# RK3399_SDRAM.net
KiCad netlist of a schematic drawn in Altium Designer
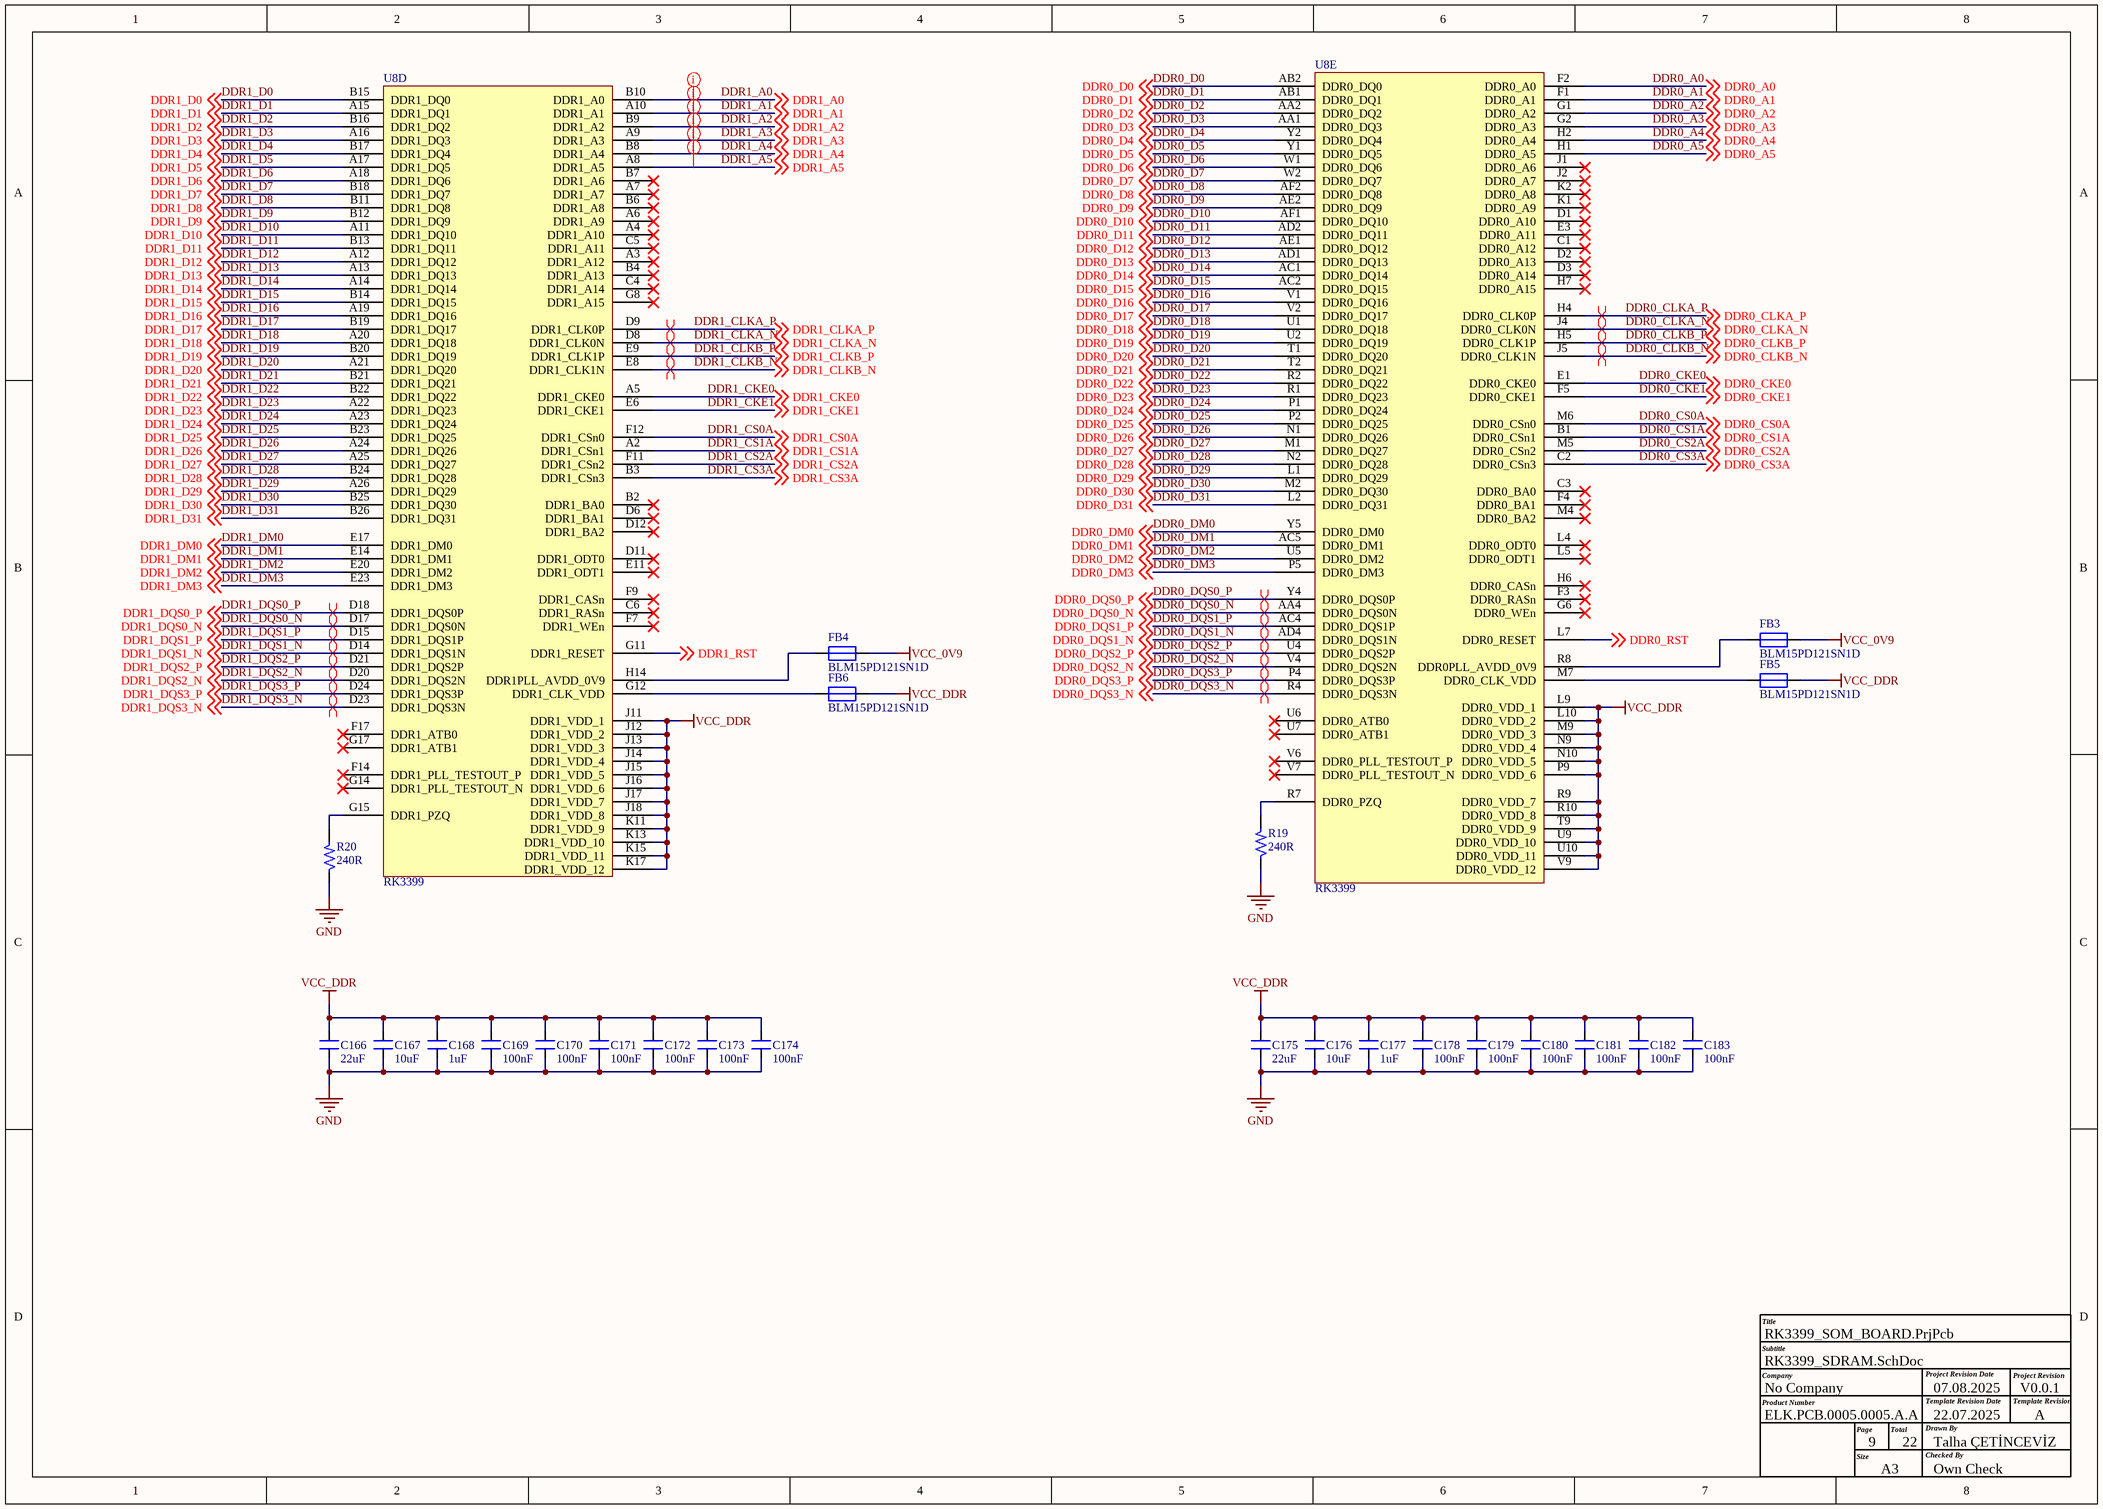
[diagram p0: RK3399_SDRAM.SchDoc]

(export (version "E")
  (design (tool "Eeschema 10.0.6"))
  (components
    (comp (ref "C166")
      (value "22uF")
      (footprint "CAP_0402")
      (description "22µF ±20% 6.3V Ceramic Capacitor X5R 0402 (1005 Metric)")
      (fields
        (field (name "MANUFACTURER") "Murata Electronics")
        (field (name "MANUFACTURER PART NUMBER") "CL05A226MQ5N6J8")
      )
      (libsource (lib "EsteemPCB_SOM_Course_intlib") (part "CAP_22uF-6.3V-20%-0402"))
    )
    (comp (ref "C167")
      (value "10uF")
      (footprint "CAP_0402")
      (description "10µF ±20% 10V Ceramic Capacitor X5R 0402 (1005 Metric)")
      (fields
        (field (name "MANUFACTURER PART NUMBER") "CL05A106MP5NUNC")
        (field (name "MANUFACTURER") "Samsung Electro-Mechanics")
      )
      (libsource (lib "EsteemPCB_SOM_Course_intlib") (part "CAP_10uF-10V-20%-0402"))
    )
    (comp (ref "C168")
      (value "1uF")
      (footprint "CAP_0201")
      (description "1µF ±20% 16V Ceramic Capacitor X5R 0201 (0603 Metric)")
      (fields
        (field (name "MANUFACTURER") "Samsung Electro-Mechanics")
        (field (name "MANUFACTURER PART NUMBER") "CL03A105MO3NRNH")
      )
      (libsource (lib "EsteemPCB_SOM_Course_intlib") (part "CAP_1uF-16V-10%-0201"))
    )
    (comp (ref "C169")
      (value "100nF")
      (footprint "CAP_0201")
      (description "0.1µF ±10% 25V Ceramic Capacitor X5R 0201 (0603 Metric)")
      (fields
        (field (name "MANUFACTURER") "TDK Corporation")
        (field (name "MANUFACTURER PART NUMBER") "C0603X5R1E104K030BB")
      )
      (libsource (lib "EsteemPCB_SOM_Course_intlib") (part "CAP_100nF-25V-10%-0201"))
    )
    (comp (ref "C170")
      (value "100nF")
      (footprint "CAP_0201")
      (description "0.1µF ±10% 25V Ceramic Capacitor X5R 0201 (0603 Metric)")
      (fields
        (field (name "MANUFACTURER") "TDK Corporation")
        (field (name "MANUFACTURER PART NUMBER") "C0603X5R1E104K030BB")
      )
      (libsource (lib "EsteemPCB_SOM_Course_intlib") (part "CAP_100nF-25V-10%-0201"))
    )
    (comp (ref "C171")
      (value "100nF")
      (footprint "CAP_0201")
      (description "0.1µF ±10% 25V Ceramic Capacitor X5R 0201 (0603 Metric)")
      (fields
        (field (name "MANUFACTURER") "TDK Corporation")
        (field (name "MANUFACTURER PART NUMBER") "C0603X5R1E104K030BB")
      )
      (libsource (lib "EsteemPCB_SOM_Course_intlib") (part "CAP_100nF-25V-10%-0201"))
    )
    (comp (ref "C172")
      (value "100nF")
      (footprint "CAP_0201")
      (description "0.1µF ±10% 25V Ceramic Capacitor X5R 0201 (0603 Metric)")
      (fields
        (field (name "MANUFACTURER") "TDK Corporation")
        (field (name "MANUFACTURER PART NUMBER") "C0603X5R1E104K030BB")
      )
      (libsource (lib "EsteemPCB_SOM_Course_intlib") (part "CAP_100nF-25V-10%-0201"))
    )
    (comp (ref "C173")
      (value "100nF")
      (footprint "CAP_0201")
      (description "0.1µF ±10% 25V Ceramic Capacitor X5R 0201 (0603 Metric)")
      (fields
        (field (name "MANUFACTURER") "TDK Corporation")
        (field (name "MANUFACTURER PART NUMBER") "C0603X5R1E104K030BB")
      )
      (libsource (lib "EsteemPCB_SOM_Course_intlib") (part "CAP_100nF-25V-10%-0201"))
    )
    (comp (ref "C174")
      (value "100nF")
      (footprint "CAP_0201")
      (description "0.1µF ±10% 25V Ceramic Capacitor X5R 0201 (0603 Metric)")
      (fields
        (field (name "MANUFACTURER") "TDK Corporation")
        (field (name "MANUFACTURER PART NUMBER") "C0603X5R1E104K030BB")
      )
      (libsource (lib "EsteemPCB_SOM_Course_intlib") (part "CAP_100nF-25V-10%-0201"))
    )
    (comp (ref "C175")
      (value "22uF")
      (footprint "CAP_0402")
      (description "22µF ±20% 6.3V Ceramic Capacitor X5R 0402 (1005 Metric)")
      (fields
        (field (name "MANUFACTURER") "Murata Electronics")
        (field (name "MANUFACTURER PART NUMBER") "CL05A226MQ5N6J8")
      )
      (libsource (lib "EsteemPCB_SOM_Course_intlib") (part "CAP_22uF-6.3V-20%-0402"))
    )
    (comp (ref "C176")
      (value "10uF")
      (footprint "CAP_0402")
      (description "10µF ±20% 10V Ceramic Capacitor X5R 0402 (1005 Metric)")
      (fields
        (field (name "MANUFACTURER PART NUMBER") "CL05A106MP5NUNC")
        (field (name "MANUFACTURER") "Samsung Electro-Mechanics")
      )
      (libsource (lib "EsteemPCB_SOM_Course_intlib") (part "CAP_10uF-10V-20%-0402"))
    )
    (comp (ref "C177")
      (value "1uF")
      (footprint "CAP_0201")
      (description "1µF ±20% 16V Ceramic Capacitor X5R 0201 (0603 Metric)")
      (fields
        (field (name "MANUFACTURER") "Samsung Electro-Mechanics")
        (field (name "MANUFACTURER PART NUMBER") "CL03A105MO3NRNH")
      )
      (libsource (lib "EsteemPCB_SOM_Course_intlib") (part "CAP_1uF-16V-10%-0201"))
    )
    (comp (ref "C178")
      (value "100nF")
      (footprint "CAP_0201")
      (description "0.1µF ±10% 25V Ceramic Capacitor X5R 0201 (0603 Metric)")
      (fields
        (field (name "MANUFACTURER") "TDK Corporation")
        (field (name "MANUFACTURER PART NUMBER") "C0603X5R1E104K030BB")
      )
      (libsource (lib "EsteemPCB_SOM_Course_intlib") (part "CAP_100nF-25V-10%-0201"))
    )
    (comp (ref "C179")
      (value "100nF")
      (footprint "CAP_0201")
      (description "0.1µF ±10% 25V Ceramic Capacitor X5R 0201 (0603 Metric)")
      (fields
        (field (name "MANUFACTURER") "TDK Corporation")
        (field (name "MANUFACTURER PART NUMBER") "C0603X5R1E104K030BB")
      )
      (libsource (lib "EsteemPCB_SOM_Course_intlib") (part "CAP_100nF-25V-10%-0201"))
    )
    (comp (ref "C180")
      (value "100nF")
      (footprint "CAP_0201")
      (description "0.1µF ±10% 25V Ceramic Capacitor X5R 0201 (0603 Metric)")
      (fields
        (field (name "MANUFACTURER") "TDK Corporation")
        (field (name "MANUFACTURER PART NUMBER") "C0603X5R1E104K030BB")
      )
      (libsource (lib "EsteemPCB_SOM_Course_intlib") (part "CAP_100nF-25V-10%-0201"))
    )
    (comp (ref "C181")
      (value "100nF")
      (footprint "CAP_0201")
      (description "0.1µF ±10% 25V Ceramic Capacitor X5R 0201 (0603 Metric)")
      (fields
        (field (name "MANUFACTURER") "TDK Corporation")
        (field (name "MANUFACTURER PART NUMBER") "C0603X5R1E104K030BB")
      )
      (libsource (lib "EsteemPCB_SOM_Course_intlib") (part "CAP_100nF-25V-10%-0201"))
    )
    (comp (ref "C182")
      (value "100nF")
      (footprint "CAP_0201")
      (description "0.1µF ±10% 25V Ceramic Capacitor X5R 0201 (0603 Metric)")
      (fields
        (field (name "MANUFACTURER") "TDK Corporation")
        (field (name "MANUFACTURER PART NUMBER") "C0603X5R1E104K030BB")
      )
      (libsource (lib "EsteemPCB_SOM_Course_intlib") (part "CAP_100nF-25V-10%-0201"))
    )
    (comp (ref "C183")
      (value "100nF")
      (footprint "CAP_0201")
      (description "0.1µF ±10% 25V Ceramic Capacitor X5R 0201 (0603 Metric)")
      (fields
        (field (name "MANUFACTURER") "TDK Corporation")
        (field (name "MANUFACTURER PART NUMBER") "C0603X5R1E104K030BB")
      )
      (libsource (lib "EsteemPCB_SOM_Course_intlib") (part "CAP_100nF-25V-10%-0201"))
    )
    (comp (ref "FB3")
      (value "BLM15PD121SN1D")
      (footprint "RES_0402")
      (description "120 Ohms @ 100MHz 1 Power Line Ferrite Bead 0402 (1005 Metric) 1.3A 90mOhm")
      (fields (field (name "MANUFACTURER") "Murata Electronics"))
      (libsource (lib "EsteemPCB_SOM_Course_intlib") (part "FB_120R-1.3A-100Mhz-0402"))
    )
    (comp (ref "FB4")
      (value "BLM15PD121SN1D")
      (footprint "RES_0402")
      (description "120 Ohms @ 100MHz 1 Power Line Ferrite Bead 0402 (1005 Metric) 1.3A 90mOhm")
      (fields (field (name "MANUFACTURER") "Murata Electronics"))
      (libsource (lib "EsteemPCB_SOM_Course_intlib") (part "FB_120R-1.3A-100Mhz-0402"))
    )
    (comp (ref "FB5")
      (value "BLM15PD121SN1D")
      (footprint "RES_0402")
      (description "120 Ohms @ 100MHz 1 Power Line Ferrite Bead 0402 (1005 Metric) 1.3A 90mOhm")
      (fields (field (name "MANUFACTURER") "Murata Electronics"))
      (libsource (lib "EsteemPCB_SOM_Course_intlib") (part "FB_120R-1.3A-100Mhz-0402"))
    )
    (comp (ref "FB6")
      (value "BLM15PD121SN1D")
      (footprint "RES_0402")
      (description "120 Ohms @ 100MHz 1 Power Line Ferrite Bead 0402 (1005 Metric) 1.3A 90mOhm")
      (fields (field (name "MANUFACTURER") "Murata Electronics"))
      (libsource (lib "EsteemPCB_SOM_Course_intlib") (part "FB_120R-1.3A-100Mhz-0402"))
    )
    (comp (ref "R19")
      (value "240R")
      (footprint "RES_0201")
      (description "240 Ohms ±1% 0.05W, 1/20W Chip Resistor 0201 (0603 Metric) Thick Film")
      (fields
        (field (name "MANUFACTURER") "Yageo")
        (field (name "MANUFACTURER PART NUMBER") "RC0201FR-07240RL")
      )
      (libsource (lib "EsteemPCB_SOM_Course_intlib") (part "RES_240R-0.05W-1%-0201"))
    )
    (comp (ref "R20")
      (value "240R")
      (footprint "RES_0201")
      (description "240 Ohms ±1% 0.05W, 1/20W Chip Resistor 0201 (0603 Metric) Thick Film")
      (fields
        (field (name "MANUFACTURER") "Yageo")
        (field (name "MANUFACTURER PART NUMBER") "RC0201FR-07240RL")
      )
      (libsource (lib "EsteemPCB_SOM_Course_intlib") (part "RES_240R-0.05W-1%-0201"))
    )
    (comp (ref "U8")
      (value "RK3399")
      (footprint "FBGA828_23_826X826")
      (description "RK3399 is a low power, high performance processor for computing, personal mobile.")
      (fields (field (name "MANUFACTURER") "Rockchip"))
      (libsource (lib "EsteemPCB_SOM_Course_intlib") (part "IC_RK3399-FCBGA828"))
    )
  )
  (nets
    (net (code "1") (name "DDR0_A0") (class "Default")
      (node (ref "U8") (pin "F2") (pinfunction "DDR0_A0_F2") (pintype "passive"))
    )
    (net (code "2") (name "DDR0_A1") (class "Default")
      (node (ref "U8") (pin "F1") (pinfunction "DDR0_A1_F1") (pintype "passive"))
    )
    (net (code "3") (name "DDR0_A2") (class "Default")
      (node (ref "U8") (pin "G1") (pinfunction "DDR0_A2_G1") (pintype "passive"))
    )
    (net (code "4") (name "DDR0_A3") (class "Default")
      (node (ref "U8") (pin "G2") (pinfunction "DDR0_A3_G2") (pintype "passive"))
    )
    (net (code "5") (name "DDR0_A4") (class "Default")
      (node (ref "U8") (pin "H2") (pinfunction "DDR0_A4_H2") (pintype "passive"))
    )
    (net (code "6") (name "DDR0_A5") (class "Default")
      (node (ref "U8") (pin "H1") (pinfunction "DDR0_A5_H1") (pintype "passive"))
    )
    (net (code "7") (name "DDR0_CKE0") (class "Default")
      (node (ref "U8") (pin "E1") (pinfunction "DDR0_CKE0_E1") (pintype "passive"))
    )
    (net (code "8") (name "DDR0_CKE1") (class "Default")
      (node (ref "U8") (pin "F5") (pinfunction "DDR0_CKE1_F5") (pintype "passive"))
    )
    (net (code "9") (name "DDR0_CLKA_N") (class "Default")
      (node (ref "U8") (pin "J4") (pinfunction "DDR0_CLK0N_J4") (pintype "passive"))
    )
    (net (code "10") (name "DDR0_CLKA_P") (class "Default")
      (node (ref "U8") (pin "H4") (pinfunction "DDR0_CLK0P_H4") (pintype "passive"))
    )
    (net (code "11") (name "DDR0_CLKB_N") (class "Default")
      (node (ref "U8") (pin "J5") (pinfunction "DDR0_CLK1N_J5") (pintype "passive"))
    )
    (net (code "12") (name "DDR0_CLKB_P") (class "Default")
      (node (ref "U8") (pin "H5") (pinfunction "DDR0_CLK1P_H5") (pintype "passive"))
    )
    (net (code "13") (name "DDR0_CS0A") (class "Default")
      (node (ref "U8") (pin "M6") (pinfunction "DDR0_CSn0_M6") (pintype "passive"))
    )
    (net (code "14") (name "DDR0_CS1A") (class "Default")
      (node (ref "U8") (pin "B1") (pinfunction "DDR0_CSn1_B1") (pintype "passive"))
    )
    (net (code "15") (name "DDR0_CS2A") (class "Default")
      (node (ref "U8") (pin "M5") (pinfunction "DDR0_CSn2_M5") (pintype "passive"))
    )
    (net (code "16") (name "DDR0_CS3A") (class "Default")
      (node (ref "U8") (pin "C2") (pinfunction "DDR0_CSn3_C2") (pintype "passive"))
    )
    (net (code "17") (name "DDR0_D0") (class "Default")
      (node (ref "U8") (pin "AB2") (pinfunction "DDR0_DQ0_AB2") (pintype "passive"))
    )
    (net (code "18") (name "DDR0_D1") (class "Default")
      (node (ref "U8") (pin "AB1") (pinfunction "DDR0_DQ1_AB1") (pintype "passive"))
    )
    (net (code "19") (name "DDR0_D2") (class "Default")
      (node (ref "U8") (pin "AA2") (pinfunction "DDR0_DQ2_AA2") (pintype "passive"))
    )
    (net (code "20") (name "DDR0_D3") (class "Default")
      (node (ref "U8") (pin "AA1") (pinfunction "DDR0_DQ3_AA1") (pintype "passive"))
    )
    (net (code "21") (name "DDR0_D4") (class "Default")
      (node (ref "U8") (pin "Y2") (pinfunction "DDR0_DQ4_Y2") (pintype "passive"))
    )
    (net (code "22") (name "DDR0_D5") (class "Default")
      (node (ref "U8") (pin "Y1") (pinfunction "DDR0_DQ5_Y1") (pintype "passive"))
    )
    (net (code "23") (name "DDR0_D6") (class "Default")
      (node (ref "U8") (pin "W1") (pinfunction "DDR0_DQ6_W1") (pintype "passive"))
    )
    (net (code "24") (name "DDR0_D7") (class "Default")
      (node (ref "U8") (pin "W2") (pinfunction "DDR0_DQ7_W2") (pintype "passive"))
    )
    (net (code "25") (name "DDR0_D8") (class "Default")
      (node (ref "U8") (pin "AF2") (pinfunction "DDR0_DQ8_AF2") (pintype "passive"))
    )
    (net (code "26") (name "DDR0_D9") (class "Default")
      (node (ref "U8") (pin "AE2") (pinfunction "DDR0_DQ9_AE2") (pintype "passive"))
    )
    (net (code "27") (name "DDR0_D10") (class "Default")
      (node (ref "U8") (pin "AF1") (pinfunction "DDR0_DQ10_AF1") (pintype "passive"))
    )
    (net (code "28") (name "DDR0_D11") (class "Default")
      (node (ref "U8") (pin "AD2") (pinfunction "DDR0_DQ11_AD2") (pintype "passive"))
    )
    (net (code "29") (name "DDR0_D12") (class "Default")
      (node (ref "U8") (pin "AE1") (pinfunction "DDR0_DQ12_AE1") (pintype "passive"))
    )
    (net (code "30") (name "DDR0_D13") (class "Default")
      (node (ref "U8") (pin "AD1") (pinfunction "DDR0_DQ13_AD1") (pintype "passive"))
    )
    (net (code "31") (name "DDR0_D14") (class "Default")
      (node (ref "U8") (pin "AC1") (pinfunction "DDR0_DQ14_AC1") (pintype "passive"))
    )
    (net (code "32") (name "DDR0_D15") (class "Default")
      (node (ref "U8") (pin "AC2") (pinfunction "DDR0_DQ15_AC2") (pintype "passive"))
    )
    (net (code "33") (name "DDR0_D16") (class "Default")
      (node (ref "U8") (pin "V1") (pinfunction "DDR0_DQ16_V1") (pintype "passive"))
    )
    (net (code "34") (name "DDR0_D17") (class "Default")
      (node (ref "U8") (pin "V2") (pinfunction "DDR0_DQ17_V2") (pintype "passive"))
    )
    (net (code "35") (name "DDR0_D18") (class "Default")
      (node (ref "U8") (pin "U1") (pinfunction "DDR0_DQ18_U1") (pintype "passive"))
    )
    (net (code "36") (name "DDR0_D19") (class "Default")
      (node (ref "U8") (pin "U2") (pinfunction "DDR0_DQ19_U2") (pintype "passive"))
    )
    (net (code "37") (name "DDR0_D20") (class "Default")
      (node (ref "U8") (pin "T1") (pinfunction "DDR0_DQ20_T1") (pintype "passive"))
    )
    (net (code "38") (name "DDR0_D21") (class "Default")
      (node (ref "U8") (pin "T2") (pinfunction "DDR0_DQ21_T2") (pintype "passive"))
    )
    (net (code "39") (name "DDR0_D22") (class "Default")
      (node (ref "U8") (pin "R2") (pinfunction "DDR0_DQ22_R2") (pintype "passive"))
    )
    (net (code "40") (name "DDR0_D23") (class "Default")
      (node (ref "U8") (pin "R1") (pinfunction "DDR0_DQ23_R1") (pintype "passive"))
    )
    (net (code "41") (name "DDR0_D24") (class "Default")
      (node (ref "U8") (pin "P1") (pinfunction "DDR0_DQ24_P1") (pintype "passive"))
    )
    (net (code "42") (name "DDR0_D25") (class "Default")
      (node (ref "U8") (pin "P2") (pinfunction "DDR0_DQ25_P2") (pintype "passive"))
    )
    (net (code "43") (name "DDR0_D26") (class "Default")
      (node (ref "U8") (pin "N1") (pinfunction "DDR0_DQ26_N1") (pintype "passive"))
    )
    (net (code "44") (name "DDR0_D27") (class "Default")
      (node (ref "U8") (pin "M1") (pinfunction "DDR0_DQ27_M1") (pintype "passive"))
    )
    (net (code "45") (name "DDR0_D28") (class "Default")
      (node (ref "U8") (pin "N2") (pinfunction "DDR0_DQ28_N2") (pintype "passive"))
    )
    (net (code "46") (name "DDR0_D29") (class "Default")
      (node (ref "U8") (pin "L1") (pinfunction "DDR0_DQ29_L1") (pintype "passive"))
    )
    (net (code "47") (name "DDR0_D30") (class "Default")
      (node (ref "U8") (pin "M2") (pinfunction "DDR0_DQ30_M2") (pintype "passive"))
    )
    (net (code "48") (name "DDR0_D31") (class "Default")
      (node (ref "U8") (pin "L2") (pinfunction "DDR0_DQ31_L2") (pintype "passive"))
    )
    (net (code "49") (name "DDR0_DM0") (class "Default")
      (node (ref "U8") (pin "Y5") (pinfunction "DDR0_DM0_Y5") (pintype "passive"))
    )
    (net (code "50") (name "DDR0_DM1") (class "Default")
      (node (ref "U8") (pin "AC5") (pinfunction "DDR0_DM1_AC5") (pintype "passive"))
    )
    (net (code "51") (name "DDR0_DM2") (class "Default")
      (node (ref "U8") (pin "U5") (pinfunction "DDR0_DM2_U5") (pintype "passive"))
    )
    (net (code "52") (name "DDR0_DM3") (class "Default")
      (node (ref "U8") (pin "P5") (pinfunction "DDR0_DM3_P5") (pintype "passive"))
    )
    (net (code "53") (name "DDR0_DQS0_N") (class "Default")
      (node (ref "U8") (pin "AA4") (pinfunction "DDR0_DQS0N_AA4") (pintype "passive"))
    )
    (net (code "54") (name "DDR0_DQS0_P") (class "Default")
      (node (ref "U8") (pin "Y4") (pinfunction "DDR0_DQS0P_Y4") (pintype "passive"))
    )
    (net (code "55") (name "DDR0_DQS1_N") (class "Default")
      (node (ref "U8") (pin "AD4") (pinfunction "DDR0_DQS1N_AD4") (pintype "passive"))
    )
    (net (code "56") (name "DDR0_DQS1_P") (class "Default")
      (node (ref "U8") (pin "AC4") (pinfunction "DDR0_DQS1P_AC4") (pintype "passive"))
    )
    (net (code "57") (name "DDR0_DQS2_N") (class "Default")
      (node (ref "U8") (pin "V4") (pinfunction "DDR0_DQS2N_V4") (pintype "passive"))
    )
    (net (code "58") (name "DDR0_DQS2_P") (class "Default")
      (node (ref "U8") (pin "U4") (pinfunction "DDR0_DQS2P_U4") (pintype "passive"))
    )
    (net (code "59") (name "DDR0_DQS3_N") (class "Default")
      (node (ref "U8") (pin "R4") (pinfunction "DDR0_DQS3N_R4") (pintype "passive"))
    )
    (net (code "60") (name "DDR0_DQS3_P") (class "Default")
      (node (ref "U8") (pin "P4") (pinfunction "DDR0_DQS3P_P4") (pintype "passive"))
    )
    (net (code "61") (name "DDR0_RST") (class "Default")
      (node (ref "U8") (pin "L7") (pinfunction "DDR0_RESET_L7") (pintype "passive"))
    )
    (net (code "62") (name "DDR1_A0") (class "Default")
      (node (ref "U8") (pin "B10") (pinfunction "DDR1_A0_B10") (pintype "passive"))
    )
    (net (code "63") (name "DDR1_A1") (class "Default")
      (node (ref "U8") (pin "A10") (pinfunction "DDR1_A1_A10") (pintype "passive"))
    )
    (net (code "64") (name "DDR1_A2") (class "Default")
      (node (ref "U8") (pin "B9") (pinfunction "DDR1_A2_B9") (pintype "passive"))
    )
    (net (code "65") (name "DDR1_A3") (class "Default")
      (node (ref "U8") (pin "A9") (pinfunction "DDR1_A3_A9") (pintype "passive"))
    )
    (net (code "66") (name "DDR1_A4") (class "Default")
      (node (ref "U8") (pin "B8") (pinfunction "DDR1_A4_B8") (pintype "passive"))
    )
    (net (code "67") (name "DDR1_A5") (class "Default")
      (node (ref "U8") (pin "A8") (pinfunction "DDR1_A5_A8") (pintype "passive"))
    )
    (net (code "68") (name "DDR1_CKE0") (class "Default")
      (node (ref "U8") (pin "A5") (pinfunction "DDR1_CKE0_A5") (pintype "passive"))
    )
    (net (code "69") (name "DDR1_CKE1") (class "Default")
      (node (ref "U8") (pin "E6") (pinfunction "DDR1_CKE1_E6") (pintype "passive"))
    )
    (net (code "70") (name "DDR1_CLKA_N") (class "Default")
      (node (ref "U8") (pin "D8") (pinfunction "DDR1_CLK0N_D8") (pintype "passive"))
    )
    (net (code "71") (name "DDR1_CLKA_P") (class "Default")
      (node (ref "U8") (pin "D9") (pinfunction "DDR1_CLK0P_D9") (pintype "passive"))
    )
    (net (code "72") (name "DDR1_CLKB_N") (class "Default")
      (node (ref "U8") (pin "E8") (pinfunction "DDR1_CLK1N_E8") (pintype "passive"))
    )
    (net (code "73") (name "DDR1_CLKB_P") (class "Default")
      (node (ref "U8") (pin "E9") (pinfunction "DDR1_CLK1P_E9") (pintype "passive"))
    )
    (net (code "74") (name "DDR1_CS0A") (class "Default")
      (node (ref "U8") (pin "F12") (pinfunction "DDR1_CSn0_F12") (pintype "passive"))
    )
    (net (code "75") (name "DDR1_CS1A") (class "Default")
      (node (ref "U8") (pin "A2") (pinfunction "DDR1_CSn1_A2") (pintype "passive"))
    )
    (net (code "76") (name "DDR1_CS2A") (class "Default")
      (node (ref "U8") (pin "F11") (pinfunction "DDR1_CSn2_F11") (pintype "passive"))
    )
    (net (code "77") (name "DDR1_CS3A") (class "Default")
      (node (ref "U8") (pin "B3") (pinfunction "DDR1_CSn3_B3") (pintype "passive"))
    )
    (net (code "78") (name "DDR1_D0") (class "Default")
      (node (ref "U8") (pin "B15") (pinfunction "DDR1_DQ0_B15") (pintype "passive"))
    )
    (net (code "79") (name "DDR1_D1") (class "Default")
      (node (ref "U8") (pin "A15") (pinfunction "DDR1_DQ1_A15") (pintype "passive"))
    )
    (net (code "80") (name "DDR1_D2") (class "Default")
      (node (ref "U8") (pin "B16") (pinfunction "DDR1_DQ2_B16") (pintype "passive"))
    )
    (net (code "81") (name "DDR1_D3") (class "Default")
      (node (ref "U8") (pin "A16") (pinfunction "DDR1_DQ3_A16") (pintype "passive"))
    )
    (net (code "82") (name "DDR1_D4") (class "Default")
      (node (ref "U8") (pin "B17") (pinfunction "DDR1_DQ4_B17") (pintype "passive"))
    )
    (net (code "83") (name "DDR1_D5") (class "Default")
      (node (ref "U8") (pin "A17") (pinfunction "DDR1_DQ5_A17") (pintype "passive"))
    )
    (net (code "84") (name "DDR1_D6") (class "Default")
      (node (ref "U8") (pin "A18") (pinfunction "DDR1_DQ6_A18") (pintype "passive"))
    )
    (net (code "85") (name "DDR1_D7") (class "Default")
      (node (ref "U8") (pin "B18") (pinfunction "DDR1_DQ7_B18") (pintype "passive"))
    )
    (net (code "86") (name "DDR1_D8") (class "Default")
      (node (ref "U8") (pin "B11") (pinfunction "DDR1_DQ8_B11") (pintype "passive"))
    )
    (net (code "87") (name "DDR1_D9") (class "Default")
      (node (ref "U8") (pin "B12") (pinfunction "DDR1_DQ9_B12") (pintype "passive"))
    )
    (net (code "88") (name "DDR1_D10") (class "Default")
      (node (ref "U8") (pin "A11") (pinfunction "DDR1_DQ10_A11") (pintype "passive"))
    )
    (net (code "89") (name "DDR1_D11") (class "Default")
      (node (ref "U8") (pin "B13") (pinfunction "DDR1_DQ11_B13") (pintype "passive"))
    )
    (net (code "90") (name "DDR1_D12") (class "Default")
      (node (ref "U8") (pin "A12") (pinfunction "DDR1_DQ12_A12") (pintype "passive"))
    )
    (net (code "91") (name "DDR1_D13") (class "Default")
      (node (ref "U8") (pin "A13") (pinfunction "DDR1_DQ13_A13") (pintype "passive"))
    )
    (net (code "92") (name "DDR1_D14") (class "Default")
      (node (ref "U8") (pin "A14") (pinfunction "DDR1_DQ14_A14") (pintype "passive"))
    )
    (net (code "93") (name "DDR1_D15") (class "Default")
      (node (ref "U8") (pin "B14") (pinfunction "DDR1_DQ15_B14") (pintype "passive"))
    )
    (net (code "94") (name "DDR1_D16") (class "Default")
      (node (ref "U8") (pin "A19") (pinfunction "DDR1_DQ16_A19") (pintype "passive"))
    )
    (net (code "95") (name "DDR1_D17") (class "Default")
      (node (ref "U8") (pin "B19") (pinfunction "DDR1_DQ17_B19") (pintype "passive"))
    )
    (net (code "96") (name "DDR1_D18") (class "Default")
      (node (ref "U8") (pin "A20") (pinfunction "DDR1_DQ18_A20") (pintype "passive"))
    )
    (net (code "97") (name "DDR1_D19") (class "Default")
      (node (ref "U8") (pin "B20") (pinfunction "DDR1_DQ19_B20") (pintype "passive"))
    )
    (net (code "98") (name "DDR1_D20") (class "Default")
      (node (ref "U8") (pin "A21") (pinfunction "DDR1_DQ20_A21") (pintype "passive"))
    )
    (net (code "99") (name "DDR1_D21") (class "Default")
      (node (ref "U8") (pin "B21") (pinfunction "DDR1_DQ21_B21") (pintype "passive"))
    )
    (net (code "100") (name "DDR1_D22") (class "Default")
      (node (ref "U8") (pin "B22") (pinfunction "DDR1_DQ22_B22") (pintype "passive"))
    )
    (net (code "101") (name "DDR1_D23") (class "Default")
      (node (ref "U8") (pin "A22") (pinfunction "DDR1_DQ23_A22") (pintype "passive"))
    )
    (net (code "102") (name "DDR1_D24") (class "Default")
      (node (ref "U8") (pin "A23") (pinfunction "DDR1_DQ24_A23") (pintype "passive"))
    )
    (net (code "103") (name "DDR1_D25") (class "Default")
      (node (ref "U8") (pin "B23") (pinfunction "DDR1_DQ25_B23") (pintype "passive"))
    )
    (net (code "104") (name "DDR1_D26") (class "Default")
      (node (ref "U8") (pin "A24") (pinfunction "DDR1_DQ26_A24") (pintype "passive"))
    )
    (net (code "105") (name "DDR1_D27") (class "Default")
      (node (ref "U8") (pin "A25") (pinfunction "DDR1_DQ27_A25") (pintype "passive"))
    )
    (net (code "106") (name "DDR1_D28") (class "Default")
      (node (ref "U8") (pin "B24") (pinfunction "DDR1_DQ28_B24") (pintype "passive"))
    )
    (net (code "107") (name "DDR1_D29") (class "Default")
      (node (ref "U8") (pin "A26") (pinfunction "DDR1_DQ29_A26") (pintype "passive"))
    )
    (net (code "108") (name "DDR1_D30") (class "Default")
      (node (ref "U8") (pin "B25") (pinfunction "DDR1_DQ30_B25") (pintype "passive"))
    )
    (net (code "109") (name "DDR1_D31") (class "Default")
      (node (ref "U8") (pin "B26") (pinfunction "DDR1_DQ31_B26") (pintype "passive"))
    )
    (net (code "110") (name "DDR1_DM0") (class "Default")
      (node (ref "U8") (pin "E17") (pinfunction "DDR1_DM0_E17") (pintype "passive"))
    )
    (net (code "111") (name "DDR1_DM1") (class "Default")
      (node (ref "U8") (pin "E14") (pinfunction "DDR1_DM1_E14") (pintype "passive"))
    )
    (net (code "112") (name "DDR1_DM2") (class "Default")
      (node (ref "U8") (pin "E20") (pinfunction "DDR1_DM2_E20") (pintype "passive"))
    )
    (net (code "113") (name "DDR1_DM3") (class "Default")
      (node (ref "U8") (pin "E23") (pinfunction "DDR1_DM3_E23") (pintype "passive"))
    )
    (net (code "114") (name "DDR1_DQS0_N") (class "Default")
      (node (ref "U8") (pin "D17") (pinfunction "DDR1_DQS0N_D17") (pintype "passive"))
    )
    (net (code "115") (name "DDR1_DQS0_P") (class "Default")
      (node (ref "U8") (pin "D18") (pinfunction "DDR1_DQS0P_D18") (pintype "passive"))
    )
    (net (code "116") (name "DDR1_DQS1_N") (class "Default")
      (node (ref "U8") (pin "D14") (pinfunction "DDR1_DQS1N_D14") (pintype "passive"))
    )
    (net (code "117") (name "DDR1_DQS1_P") (class "Default")
      (node (ref "U8") (pin "D15") (pinfunction "DDR1_DQS1P_D15") (pintype "passive"))
    )
    (net (code "118") (name "DDR1_DQS2_N") (class "Default")
      (node (ref "U8") (pin "D20") (pinfunction "DDR1_DQS2N_D20") (pintype "passive"))
    )
    (net (code "119") (name "DDR1_DQS2_P") (class "Default")
      (node (ref "U8") (pin "D21") (pinfunction "DDR1_DQS2P_D21") (pintype "passive"))
    )
    (net (code "120") (name "DDR1_DQS3_N") (class "Default")
      (node (ref "U8") (pin "D23") (pinfunction "DDR1_DQS3N_D23") (pintype "passive"))
    )
    (net (code "121") (name "DDR1_DQS3_P") (class "Default")
      (node (ref "U8") (pin "D24") (pinfunction "DDR1_DQS3P_D24") (pintype "passive"))
    )
    (net (code "122") (name "DDR1_RST") (class "Default")
      (node (ref "U8") (pin "G11") (pinfunction "DDR1_RESET_G11") (pintype "passive"))
    )
    (net (code "123") (name "GND") (class "Default")
      (node (ref "C166") (pin "1") (pinfunction "1_1") (pintype "passive"))
      (node (ref "C167") (pin "1") (pinfunction "1_1") (pintype "passive"))
      (node (ref "C168") (pin "1") (pinfunction "1_1") (pintype "passive"))
      (node (ref "C169") (pin "1") (pinfunction "1_1") (pintype "passive"))
      (node (ref "C170") (pin "1") (pinfunction "1_1") (pintype "passive"))
      (node (ref "C171") (pin "1") (pinfunction "1_1") (pintype "passive"))
      (node (ref "C172") (pin "1") (pinfunction "1_1") (pintype "passive"))
      (node (ref "C173") (pin "1") (pinfunction "1_1") (pintype "passive"))
      (node (ref "C174") (pin "1") (pinfunction "1_1") (pintype "passive"))
      (node (ref "C175") (pin "1") (pinfunction "1_1") (pintype "passive"))
      (node (ref "C176") (pin "1") (pinfunction "1_1") (pintype "passive"))
      (node (ref "C177") (pin "1") (pinfunction "1_1") (pintype "passive"))
      (node (ref "C178") (pin "1") (pinfunction "1_1") (pintype "passive"))
      (node (ref "C179") (pin "1") (pinfunction "1_1") (pintype "passive"))
      (node (ref "C180") (pin "1") (pinfunction "1_1") (pintype "passive"))
      (node (ref "C181") (pin "1") (pinfunction "1_1") (pintype "passive"))
      (node (ref "C182") (pin "1") (pinfunction "1_1") (pintype "passive"))
      (node (ref "C183") (pin "1") (pinfunction "1_1") (pintype "passive"))
      (node (ref "R19") (pin "1") (pinfunction "1_1") (pintype "passive"))
      (node (ref "R20") (pin "1") (pinfunction "1_1") (pintype "passive"))
    )
    (net (code "124") (name "Net-(U8D-DDR1PLL_AVDD_0V9)") (class "Default")
      (node (ref "FB4") (pin "1") (pinfunction "1_1") (pintype "passive"))
      (node (ref "U8") (pin "H14") (pinfunction "DDR1PLL_AVDD_0V9_H14") (pintype "passive"))
    )
    (net (code "125") (name "Net-(U8D-DDR1_CLK_VDD)") (class "Default")
      (node (ref "FB6") (pin "1") (pinfunction "1_1") (pintype "passive"))
      (node (ref "U8") (pin "G12") (pinfunction "DDR1_CLK_VDD_G12") (pintype "passive"))
    )
    (net (code "126") (name "Net-(U8D-DDR1_PZQ)") (class "Default")
      (node (ref "R20") (pin "2") (pinfunction "2_2") (pintype "passive"))
      (node (ref "U8") (pin "G15") (pinfunction "DDR1_PZQ_G15") (pintype "passive"))
    )
    (net (code "127") (name "Net-(U8E-DDR0PLL_AVDD_0V9)") (class "Default")
      (node (ref "FB3") (pin "1") (pinfunction "1_1") (pintype "passive"))
      (node (ref "U8") (pin "R8") (pinfunction "DDR0PLL_AVDD_0V9_R8") (pintype "passive"))
    )
    (net (code "128") (name "Net-(U8E-DDR0_CLK_VDD)") (class "Default")
      (node (ref "FB5") (pin "1") (pinfunction "1_1") (pintype "passive"))
      (node (ref "U8") (pin "M7") (pinfunction "DDR0_CLK_VDD_M7") (pintype "passive"))
    )
    (net (code "129") (name "Net-(U8E-DDR0_PZQ)") (class "Default")
      (node (ref "R19") (pin "2") (pinfunction "2_2") (pintype "passive"))
      (node (ref "U8") (pin "R7") (pinfunction "DDR0_PZQ_R7") (pintype "passive"))
    )
    (net (code "130") (name "VCC_0V9") (class "Default")
      (node (ref "FB3") (pin "2") (pinfunction "2_2") (pintype "passive"))
      (node (ref "FB4") (pin "2") (pinfunction "2_2") (pintype "passive"))
    )
    (net (code "131") (name "VCC_DDR") (class "Default")
      (node (ref "C166") (pin "2") (pinfunction "2_2") (pintype "passive"))
      (node (ref "C167") (pin "2") (pinfunction "2_2") (pintype "passive"))
      (node (ref "C168") (pin "2") (pinfunction "2_2") (pintype "passive"))
      (node (ref "C169") (pin "2") (pinfunction "2_2") (pintype "passive"))
      (node (ref "C170") (pin "2") (pinfunction "2_2") (pintype "passive"))
      (node (ref "C171") (pin "2") (pinfunction "2_2") (pintype "passive"))
      (node (ref "C172") (pin "2") (pinfunction "2_2") (pintype "passive"))
      (node (ref "C173") (pin "2") (pinfunction "2_2") (pintype "passive"))
      (node (ref "C174") (pin "2") (pinfunction "2_2") (pintype "passive"))
      (node (ref "C175") (pin "2") (pinfunction "2_2") (pintype "passive"))
      (node (ref "C176") (pin "2") (pinfunction "2_2") (pintype "passive"))
      (node (ref "C177") (pin "2") (pinfunction "2_2") (pintype "passive"))
      (node (ref "C178") (pin "2") (pinfunction "2_2") (pintype "passive"))
      (node (ref "C179") (pin "2") (pinfunction "2_2") (pintype "passive"))
      (node (ref "C180") (pin "2") (pinfunction "2_2") (pintype "passive"))
      (node (ref "C181") (pin "2") (pinfunction "2_2") (pintype "passive"))
      (node (ref "C182") (pin "2") (pinfunction "2_2") (pintype "passive"))
      (node (ref "C183") (pin "2") (pinfunction "2_2") (pintype "passive"))
      (node (ref "FB5") (pin "2") (pinfunction "2_2") (pintype "passive"))
      (node (ref "FB6") (pin "2") (pinfunction "2_2") (pintype "passive"))
      (node (ref "U8") (pin "J11") (pinfunction "DDR1_VDD_1_J11") (pintype "passive"))
      (node (ref "U8") (pin "J12") (pinfunction "DDR1_VDD_2_J12") (pintype "passive"))
      (node (ref "U8") (pin "J13") (pinfunction "DDR1_VDD_3_J13") (pintype "passive"))
      (node (ref "U8") (pin "J14") (pinfunction "DDR1_VDD_4_J14") (pintype "passive"))
      (node (ref "U8") (pin "J15") (pinfunction "DDR1_VDD_5_J15") (pintype "passive"))
      (node (ref "U8") (pin "J16") (pinfunction "DDR1_VDD_6_J16") (pintype "passive"))
      (node (ref "U8") (pin "J17") (pinfunction "DDR1_VDD_7_J17") (pintype "passive"))
      (node (ref "U8") (pin "J18") (pinfunction "DDR1_VDD_8_J18") (pintype "passive"))
      (node (ref "U8") (pin "K11") (pinfunction "DDR1_VDD_9_K11") (pintype "passive"))
      (node (ref "U8") (pin "K13") (pinfunction "DDR1_VDD_10_K13") (pintype "passive"))
      (node (ref "U8") (pin "K15") (pinfunction "DDR1_VDD_11_K15") (pintype "passive"))
      (node (ref "U8") (pin "K17") (pinfunction "DDR1_VDD_12_K17") (pintype "passive"))
      (node (ref "U8") (pin "L10") (pinfunction "DDR0_VDD_2_L10") (pintype "passive"))
      (node (ref "U8") (pin "L9") (pinfunction "DDR0_VDD_1_L9") (pintype "passive"))
      (node (ref "U8") (pin "M9") (pinfunction "DDR0_VDD_3_M9") (pintype "passive"))
      (node (ref "U8") (pin "N10") (pinfunction "DDR0_VDD_5_N10") (pintype "passive"))
      (node (ref "U8") (pin "N9") (pinfunction "DDR0_VDD_4_N9") (pintype "passive"))
      (node (ref "U8") (pin "P9") (pinfunction "DDR0_VDD_6_P9") (pintype "passive"))
      (node (ref "U8") (pin "R10") (pinfunction "DDR0_VDD_8_R10") (pintype "passive"))
      (node (ref "U8") (pin "R9") (pinfunction "DDR0_VDD_7_R9") (pintype "passive"))
      (node (ref "U8") (pin "T9") (pinfunction "DDR0_VDD_9_T9") (pintype "passive"))
      (node (ref "U8") (pin "U10") (pinfunction "DDR0_VDD_11_U10") (pintype "passive"))
      (node (ref "U8") (pin "U9") (pinfunction "DDR0_VDD_10_U9") (pintype "passive"))
      (node (ref "U8") (pin "V9") (pinfunction "DDR0_VDD_12_V9") (pintype "passive"))
    )
    (net (code "132") (name "unconnected-(U8D-DDR1_A6-PadB7)") (class "Default")
      (node (ref "U8") (pin "B7") (pinfunction "DDR1_A6_B7") (pintype "passive+no_connect"))
    )
    (net (code "133") (name "unconnected-(U8D-DDR1_A7-PadA7)") (class "Default")
      (node (ref "U8") (pin "A7") (pinfunction "DDR1_A7_A7") (pintype "passive+no_connect"))
    )
    (net (code "134") (name "unconnected-(U8D-DDR1_A8-PadB6)") (class "Default")
      (node (ref "U8") (pin "B6") (pinfunction "DDR1_A8_B6") (pintype "passive+no_connect"))
    )
    (net (code "135") (name "unconnected-(U8D-DDR1_A9-PadA6)") (class "Default")
      (node (ref "U8") (pin "A6") (pinfunction "DDR1_A9_A6") (pintype "passive+no_connect"))
    )
    (net (code "136") (name "unconnected-(U8D-DDR1_A10-PadA4)") (class "Default")
      (node (ref "U8") (pin "A4") (pinfunction "DDR1_A10_A4") (pintype "passive+no_connect"))
    )
    (net (code "137") (name "unconnected-(U8D-DDR1_A11-PadC5)") (class "Default")
      (node (ref "U8") (pin "C5") (pinfunction "DDR1_A11_C5") (pintype "passive+no_connect"))
    )
    (net (code "138") (name "unconnected-(U8D-DDR1_A12-PadA3)") (class "Default")
      (node (ref "U8") (pin "A3") (pinfunction "DDR1_A12_A3") (pintype "passive+no_connect"))
    )
    (net (code "139") (name "unconnected-(U8D-DDR1_A13-PadB4)") (class "Default")
      (node (ref "U8") (pin "B4") (pinfunction "DDR1_A13_B4") (pintype "passive+no_connect"))
    )
    (net (code "140") (name "unconnected-(U8D-DDR1_A14-PadC4)") (class "Default")
      (node (ref "U8") (pin "C4") (pinfunction "DDR1_A14_C4") (pintype "passive+no_connect"))
    )
    (net (code "141") (name "unconnected-(U8D-DDR1_A15-PadG8)") (class "Default")
      (node (ref "U8") (pin "G8") (pinfunction "DDR1_A15_G8") (pintype "passive+no_connect"))
    )
    (net (code "142") (name "unconnected-(U8D-DDR1_ATB0-PadF17)") (class "Default")
      (node (ref "U8") (pin "F17") (pinfunction "DDR1_ATB0_F17") (pintype "passive+no_connect"))
    )
    (net (code "143") (name "unconnected-(U8D-DDR1_ATB1-PadG17)") (class "Default")
      (node (ref "U8") (pin "G17") (pinfunction "DDR1_ATB1_G17") (pintype "passive+no_connect"))
    )
    (net (code "144") (name "unconnected-(U8D-DDR1_BA0-PadB2)") (class "Default")
      (node (ref "U8") (pin "B2") (pinfunction "DDR1_BA0_B2") (pintype "passive+no_connect"))
    )
    (net (code "145") (name "unconnected-(U8D-DDR1_BA1-PadD6)") (class "Default")
      (node (ref "U8") (pin "D6") (pinfunction "DDR1_BA1_D6") (pintype "passive+no_connect"))
    )
    (net (code "146") (name "unconnected-(U8D-DDR1_BA2-PadD12)") (class "Default")
      (node (ref "U8") (pin "D12") (pinfunction "DDR1_BA2_D12") (pintype "passive+no_connect"))
    )
    (net (code "147") (name "unconnected-(U8D-DDR1_CASn-PadF9)") (class "Default")
      (node (ref "U8") (pin "F9") (pinfunction "DDR1_CASn_F9") (pintype "passive+no_connect"))
    )
    (net (code "148") (name "unconnected-(U8D-DDR1_ODT0-PadD11)") (class "Default")
      (node (ref "U8") (pin "D11") (pinfunction "DDR1_ODT0_D11") (pintype "passive+no_connect"))
    )
    (net (code "149") (name "unconnected-(U8D-DDR1_ODT1-PadE11)") (class "Default")
      (node (ref "U8") (pin "E11") (pinfunction "DDR1_ODT1_E11") (pintype "passive+no_connect"))
    )
    (net (code "150") (name "unconnected-(U8D-DDR1_PLL_TESTOUT_N-PadG14)") (class "Default")
      (node (ref "U8") (pin "G14") (pinfunction "DDR1_PLL_TESTOUT_N_G14") (pintype "passive+no_connect"))
    )
    (net (code "151") (name "unconnected-(U8D-DDR1_PLL_TESTOUT_P-PadF14)") (class "Default")
      (node (ref "U8") (pin "F14") (pinfunction "DDR1_PLL_TESTOUT_P_F14") (pintype "passive+no_connect"))
    )
    (net (code "152") (name "unconnected-(U8D-DDR1_RASn-PadC6)") (class "Default")
      (node (ref "U8") (pin "C6") (pinfunction "DDR1_RASn_C6") (pintype "passive+no_connect"))
    )
    (net (code "153") (name "unconnected-(U8D-DDR1_WEn-PadF7)") (class "Default")
      (node (ref "U8") (pin "F7") (pinfunction "DDR1_WEn_F7") (pintype "passive+no_connect"))
    )
    (net (code "154") (name "unconnected-(U8E-DDR0_A6-PadJ1)") (class "Default")
      (node (ref "U8") (pin "J1") (pinfunction "DDR0_A6_J1") (pintype "passive+no_connect"))
    )
    (net (code "155") (name "unconnected-(U8E-DDR0_A7-PadJ2)") (class "Default")
      (node (ref "U8") (pin "J2") (pinfunction "DDR0_A7_J2") (pintype "passive+no_connect"))
    )
    (net (code "156") (name "unconnected-(U8E-DDR0_A8-PadK2)") (class "Default")
      (node (ref "U8") (pin "K2") (pinfunction "DDR0_A8_K2") (pintype "passive+no_connect"))
    )
    (net (code "157") (name "unconnected-(U8E-DDR0_A9-PadK1)") (class "Default")
      (node (ref "U8") (pin "K1") (pinfunction "DDR0_A9_K1") (pintype "passive+no_connect"))
    )
    (net (code "158") (name "unconnected-(U8E-DDR0_A10-PadD1)") (class "Default")
      (node (ref "U8") (pin "D1") (pinfunction "DDR0_A10_D1") (pintype "passive+no_connect"))
    )
    (net (code "159") (name "unconnected-(U8E-DDR0_A11-PadE3)") (class "Default")
      (node (ref "U8") (pin "E3") (pinfunction "DDR0_A11_E3") (pintype "passive+no_connect"))
    )
    (net (code "160") (name "unconnected-(U8E-DDR0_A12-PadC1)") (class "Default")
      (node (ref "U8") (pin "C1") (pinfunction "DDR0_A12_C1") (pintype "passive+no_connect"))
    )
    (net (code "161") (name "unconnected-(U8E-DDR0_A13-PadD2)") (class "Default")
      (node (ref "U8") (pin "D2") (pinfunction "DDR0_A13_D2") (pintype "passive+no_connect"))
    )
    (net (code "162") (name "unconnected-(U8E-DDR0_A14-PadD3)") (class "Default")
      (node (ref "U8") (pin "D3") (pinfunction "DDR0_A14_D3") (pintype "passive+no_connect"))
    )
    (net (code "163") (name "unconnected-(U8E-DDR0_A15-PadH7)") (class "Default")
      (node (ref "U8") (pin "H7") (pinfunction "DDR0_A15_H7") (pintype "passive+no_connect"))
    )
    (net (code "164") (name "unconnected-(U8E-DDR0_ATB0-PadU6)") (class "Default")
      (node (ref "U8") (pin "U6") (pinfunction "DDR0_ATB0_U6") (pintype "passive+no_connect"))
    )
    (net (code "165") (name "unconnected-(U8E-DDR0_ATB1-PadU7)") (class "Default")
      (node (ref "U8") (pin "U7") (pinfunction "DDR0_ATB1_U7") (pintype "passive+no_connect"))
    )
    (net (code "166") (name "unconnected-(U8E-DDR0_BA0-PadC3)") (class "Default")
      (node (ref "U8") (pin "C3") (pinfunction "DDR0_BA0_C3") (pintype "passive+no_connect"))
    )
    (net (code "167") (name "unconnected-(U8E-DDR0_BA1-PadF4)") (class "Default")
      (node (ref "U8") (pin "F4") (pinfunction "DDR0_BA1_F4") (pintype "passive+no_connect"))
    )
    (net (code "168") (name "unconnected-(U8E-DDR0_BA2-PadM4)") (class "Default")
      (node (ref "U8") (pin "M4") (pinfunction "DDR0_BA2_M4") (pintype "passive+no_connect"))
    )
    (net (code "169") (name "unconnected-(U8E-DDR0_CASn-PadH6)") (class "Default")
      (node (ref "U8") (pin "H6") (pinfunction "DDR0_CASn_H6") (pintype "passive+no_connect"))
    )
    (net (code "170") (name "unconnected-(U8E-DDR0_ODT0-PadL4)") (class "Default")
      (node (ref "U8") (pin "L4") (pinfunction "DDR0_ODT0_L4") (pintype "passive+no_connect"))
    )
    (net (code "171") (name "unconnected-(U8E-DDR0_ODT1-PadL5)") (class "Default")
      (node (ref "U8") (pin "L5") (pinfunction "DDR0_ODT1_L5") (pintype "passive+no_connect"))
    )
    (net (code "172") (name "unconnected-(U8E-DDR0_PLL_TESTOUT_N-PadV7)") (class "Default")
      (node (ref "U8") (pin "V7") (pinfunction "DDR0_PLL_TESTOUT_N_V7") (pintype "passive+no_connect"))
    )
    (net (code "173") (name "unconnected-(U8E-DDR0_PLL_TESTOUT_P-PadV6)") (class "Default")
      (node (ref "U8") (pin "V6") (pinfunction "DDR0_PLL_TESTOUT_P_V6") (pintype "passive+no_connect"))
    )
    (net (code "174") (name "unconnected-(U8E-DDR0_RASn-PadF3)") (class "Default")
      (node (ref "U8") (pin "F3") (pinfunction "DDR0_RASn_F3") (pintype "passive+no_connect"))
    )
    (net (code "175") (name "unconnected-(U8E-DDR0_WEn-PadG6)") (class "Default")
      (node (ref "U8") (pin "G6") (pinfunction "DDR0_WEn_G6") (pintype "passive+no_connect"))
    )
  )
)
